# Grove_-_OLED_Display_0_96_SSD1315__v1_0.net
KiCad netlist of a schematic drawn in EAGLE
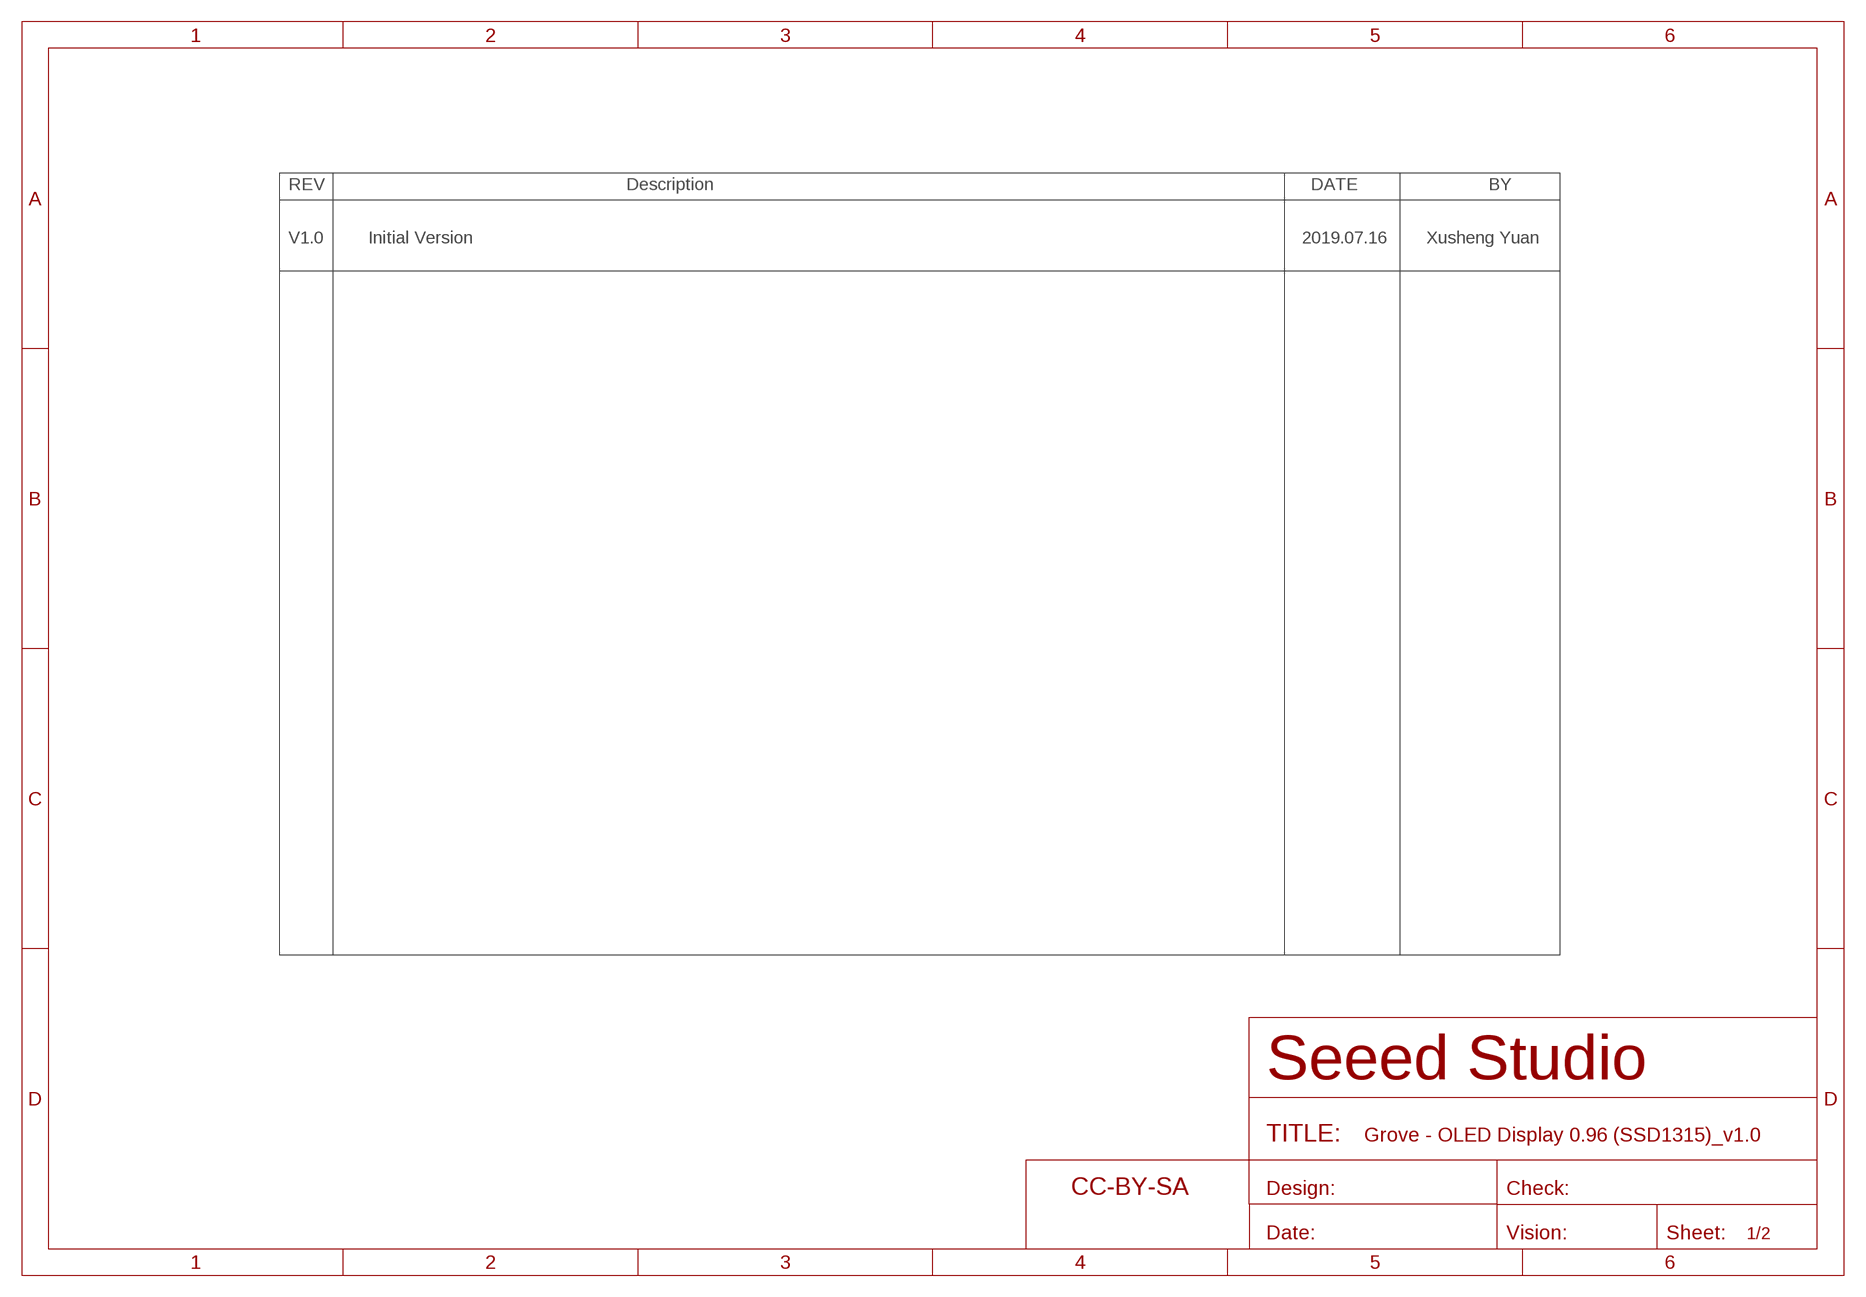
[diagram p0: schematic, sheet 1, part 1 of 2]
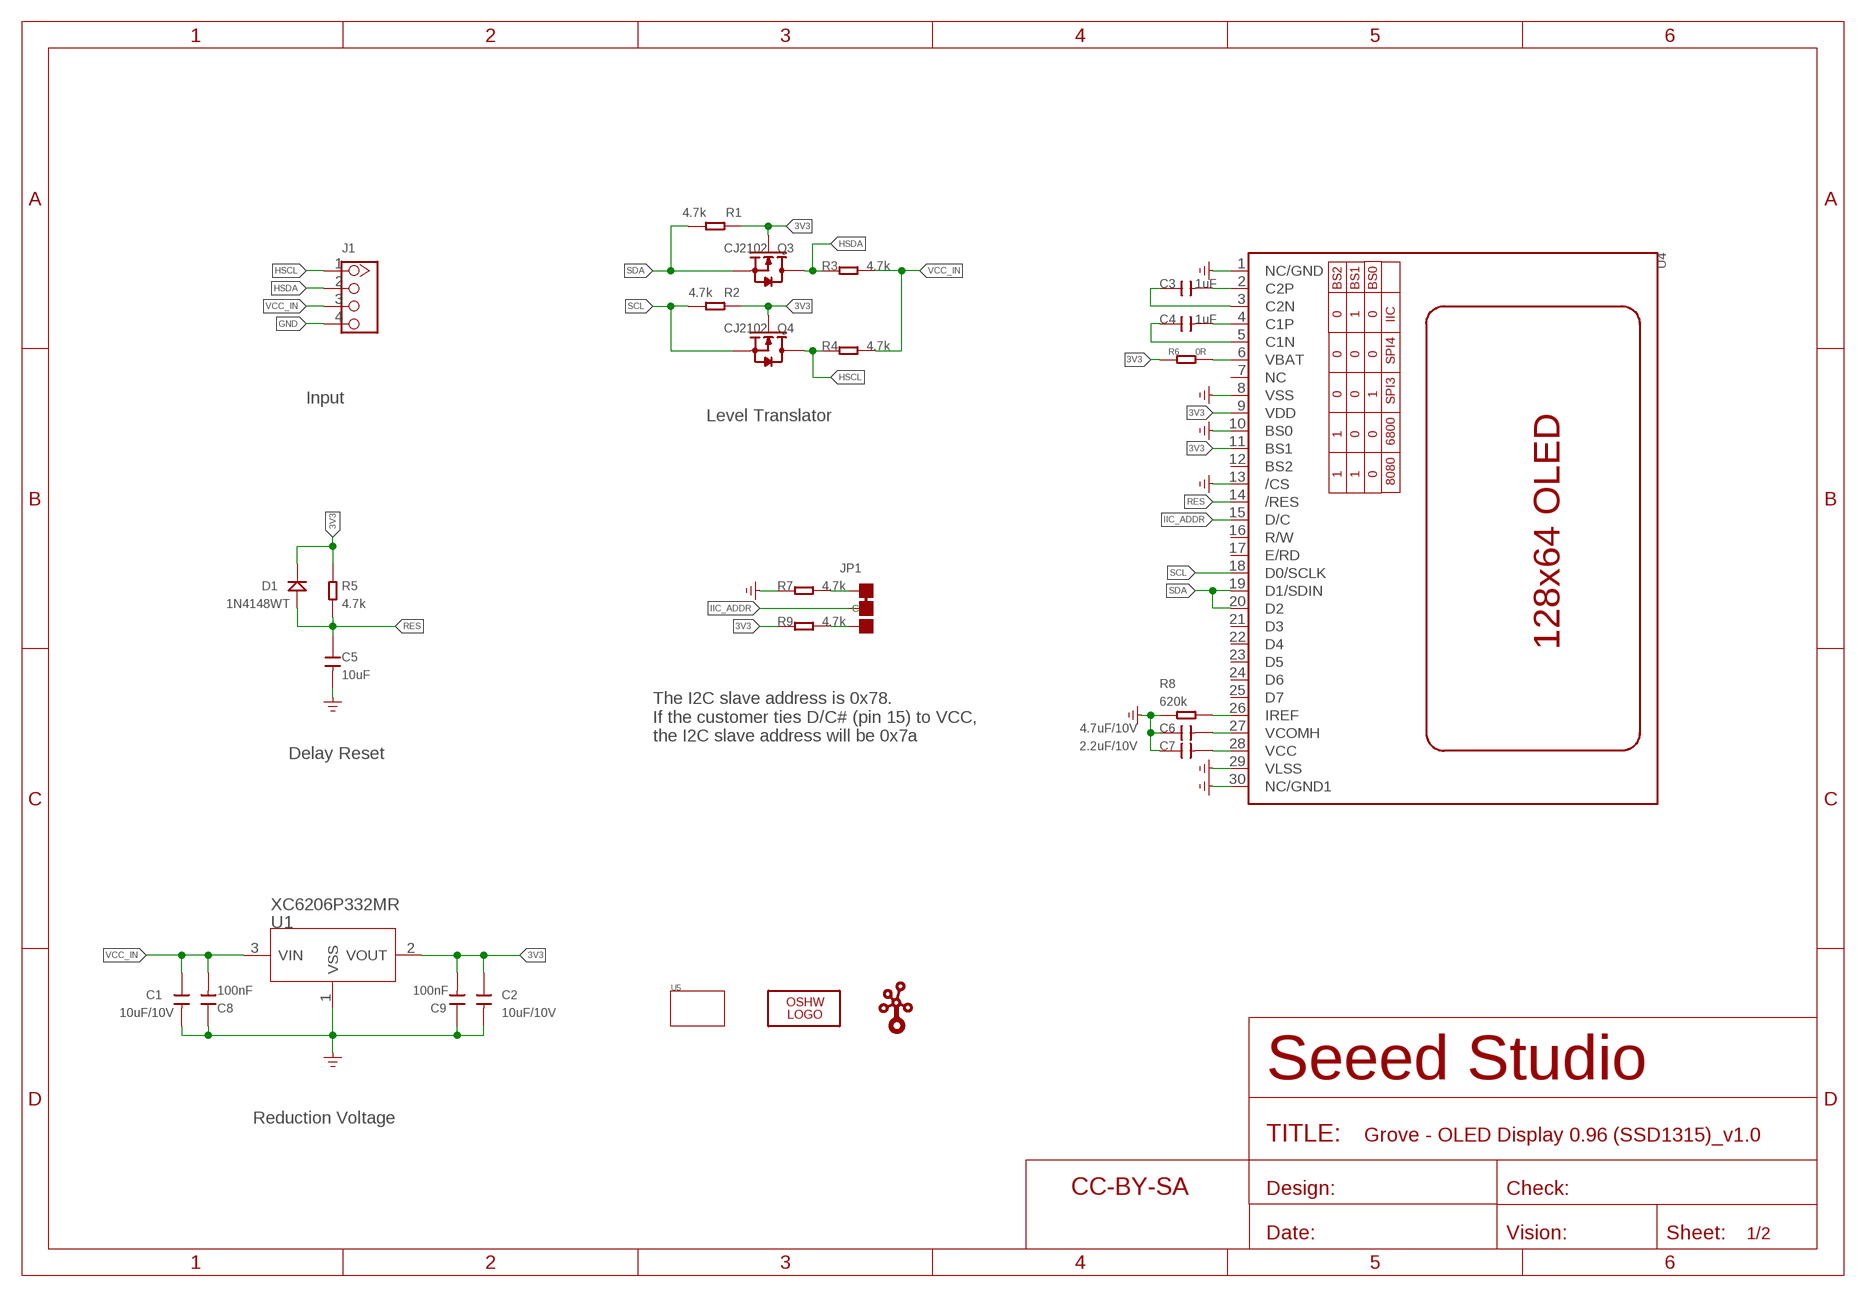
[diagram p1: schematic, sheet 1, part 2 of 2]

(export (version "E")
  (design (tool "Eeschema 10.0.6"))
  (components
    (comp (ref "C1")
      (value "10uF/10V")
      (footprint "eagle-import:C0603")
      (libsource (lib "eagle-import") (part "C-0603"))
    )
    (comp (ref "C2")
      (value "10uF/10V")
      (footprint "eagle-import:C0603")
      (libsource (lib "eagle-import") (part "C-0603"))
    )
    (comp (ref "C3")
      (value "1uF")
      (footprint "eagle-import:C0402")
      (libsource (lib "eagle-import") (part "C-0402"))
    )
    (comp (ref "C4")
      (value "1uF")
      (footprint "eagle-import:C0402")
      (libsource (lib "eagle-import") (part "C-0402"))
    )
    (comp (ref "C5")
      (value "10uF")
      (footprint "eagle-import:C0603")
      (libsource (lib "eagle-import") (part "C-0603"))
    )
    (comp (ref "C6")
      (value "4.7uF/10V")
      (footprint "eagle-import:C0603")
      (libsource (lib "eagle-import") (part "C-0603"))
    )
    (comp (ref "C7")
      (value "2.2uF/10V")
      (footprint "eagle-import:C0603")
      (libsource (lib "eagle-import") (part "C-0603"))
    )
    (comp (ref "C8")
      (value "100nF")
      (footprint "eagle-import:C0402")
      (libsource (lib "eagle-import") (part "C-0402"))
    )
    (comp (ref "C9")
      (value "100nF")
      (footprint "eagle-import:C0402")
      (libsource (lib "eagle-import") (part "C-0402"))
    )
    (comp (ref "D1")
      (value "1N4148WT")
      (footprint "eagle-import:SOD-523")
      (libsource (lib "eagle-import") (part "DIODE'0603'"))
    )
    (comp (ref "FR1")
      (value "SEEEDSTUDIO-OPEN-SCH-FRAME")
      (footprint "eagle-import:SEEEDSTUDIO-PCB-FRAME")
      (libsource (lib "eagle-import") (part "SEEEDSTUDIO-OPEN-SCH-FRAME"))
    )
    (comp (ref "FR2")
      (value "SEEEDSTUDIO-OPEN-SCH-FRAME")
      (footprint "eagle-import:SEEEDSTUDIO-PCB-FRAME")
      (libsource (lib "eagle-import") (part "SEEEDSTUDIO-OPEN-SCH-FRAME"))
    )
    (comp (ref "J1")
      (value "GROVE-CONNECTOR-DIP-320110033")
      (footprint "eagle-import:HW4-2.0")
      (libsource (lib "eagle-import") (part "GROVE-CONNECTOR-DIP-320110033"))
    )
    (comp (ref "JP1")
      (value "JP-3P-SHORT")
      (footprint "eagle-import:3P-SMD-SHORT")
      (libsource (lib "eagle-import") (part "JP-3P-SHORT"))
    )
    (comp (ref "LOGO1")
      (value "LOGO-OSHW-FILLX0150-NT")
      (footprint "eagle-import:OSHW_FILLX150_NOTEXT")
      (fields (field (name "PARTNO") "DNP"))
      (libsource (lib "eagle-import") (part "LOGO-OSHW-FILLX0150-NT"))
    )
    (comp (ref "Q3")
      (value "CJ2102")
      (footprint "eagle-import:SOT-323")
      (libsource (lib "eagle-import") (part "MOSFET-N'SI1304BDL'"))
    )
    (comp (ref "Q4")
      (value "CJ2102")
      (footprint "eagle-import:SOT-323")
      (libsource (lib "eagle-import") (part "MOSFET-N'SI1304BDL'"))
    )
    (comp (ref "R1")
      (value "4.7k")
      (footprint "eagle-import:R0402")
      (libsource (lib "eagle-import") (part "R-0402"))
    )
    (comp (ref "R2")
      (value "4.7k")
      (footprint "eagle-import:R0402")
      (libsource (lib "eagle-import") (part "R-0402"))
    )
    (comp (ref "R3")
      (value "4.7k")
      (footprint "eagle-import:R0402")
      (libsource (lib "eagle-import") (part "R-0402"))
    )
    (comp (ref "R4")
      (value "4.7k")
      (footprint "eagle-import:R0402")
      (libsource (lib "eagle-import") (part "R-0402"))
    )
    (comp (ref "R5")
      (value "4.7k")
      (footprint "eagle-import:R0402")
      (libsource (lib "eagle-import") (part "R-0402"))
    )
    (comp (ref "R6")
      (value "0R")
      (footprint "eagle-import:R0402")
      (libsource (lib "eagle-import") (part "R-0402"))
    )
    (comp (ref "R7")
      (value "4.7k")
      (footprint "eagle-import:R0402")
      (libsource (lib "eagle-import") (part "R-0402"))
    )
    (comp (ref "R8")
      (value "620k")
      (footprint "eagle-import:R0402")
      (libsource (lib "eagle-import") (part "R-0402"))
    )
    (comp (ref "R9")
      (value "4.7k")
      (footprint "eagle-import:R0402")
      (libsource (lib "eagle-import") (part "R-0402"))
    )
    (comp (ref "U$1")
      (value "LOGO-GROVETWIGLOGO_SMALL")
      (footprint "eagle-import:GROVE-SILK-SMALL")
      (fields (field (name "PARTNO") "DNP"))
      (libsource (lib "eagle-import") (part "LOGO-GROVETWIGLOGO_SMALL"))
    )
    (comp (ref "U1")
      (value "XC6206P332MR")
      (footprint "eagle-import:SOT-23")
      (libsource (lib "eagle-import") (part "PMIC-XC6206PMR"))
    )
    (comp (ref "U4")
      (value "OLED-12864-30P")
      (footprint "eagle-import:OLED30P-0.7-24.74X16.9MM")
      (libsource (lib "eagle-import") (part "OLED-12864-30P"))
    )
    (comp (ref "U5")
      (value "TWIG'2U'")
      (footprint "eagle-import:2U-DIM-W_DRILL")
      (libsource (lib "eagle-import") (part "TWIG'2U'"))
    )
  )
  (nets
    (net (code "1") (name "3V3") (class "Default")
      (node (ref "C2") (pin "1") (pinfunction "1_1") (pintype "passive"))
      (node (ref "C9") (pin "2") (pinfunction "2_2") (pintype "passive"))
      (node (ref "D1") (pin "-") (pinfunction "-_-") (pintype "passive"))
      (node (ref "Q3") (pin "1") (pinfunction "G_1") (pintype "passive"))
      (node (ref "Q4") (pin "1") (pinfunction "G_1") (pintype "passive"))
      (node (ref "R1") (pin "1") (pinfunction "1_1") (pintype "passive"))
      (node (ref "R2") (pin "2") (pinfunction "2_2") (pintype "passive"))
      (node (ref "R5") (pin "2") (pinfunction "2_2") (pintype "passive"))
      (node (ref "R6") (pin "1") (pinfunction "1_1") (pintype "passive"))
      (node (ref "R9") (pin "1") (pinfunction "1_1") (pintype "passive"))
      (node (ref "U1") (pin "2") (pinfunction "VOUT_2") (pintype "bidirectional"))
      (node (ref "U4") (pin "11") (pinfunction "BS1_11") (pintype "input"))
      (node (ref "U4") (pin "9") (pinfunction "VDD_9") (pintype "power_in"))
    )
    (net (code "2") (name "GND") (class "Default")
      (node (ref "C1") (pin "2") (pinfunction "2_2") (pintype "passive"))
      (node (ref "C2") (pin "2") (pinfunction "2_2") (pintype "passive"))
      (node (ref "C5") (pin "2") (pinfunction "2_2") (pintype "passive"))
      (node (ref "C6") (pin "1") (pinfunction "1_1") (pintype "passive"))
      (node (ref "C7") (pin "1") (pinfunction "1_1") (pintype "passive"))
      (node (ref "C8") (pin "1") (pinfunction "1_1") (pintype "passive"))
      (node (ref "C9") (pin "1") (pinfunction "1_1") (pintype "passive"))
      (node (ref "J1") (pin "4") (pinfunction "4_4") (pintype "bidirectional"))
      (node (ref "R7") (pin "1") (pinfunction "1_1") (pintype "passive"))
      (node (ref "R8") (pin "2") (pinfunction "2_2") (pintype "passive"))
      (node (ref "U1") (pin "1") (pinfunction "VSS_1") (pintype "bidirectional"))
      (node (ref "U4") (pin "1") (pinfunction "NC/GND_1") (pintype "input"))
      (node (ref "U4") (pin "10") (pinfunction "BS0_10") (pintype "input"))
      (node (ref "U4") (pin "13") (pinfunction "/CS_13") (pintype "input"))
      (node (ref "U4") (pin "29") (pinfunction "VLSS_29") (pintype "power_in"))
      (node (ref "U4") (pin "30") (pinfunction "NC/GND1_30") (pintype "input"))
      (node (ref "U4") (pin "8") (pinfunction "VSS_8") (pintype "power_in"))
    )
    (net (code "3") (name "HSCL") (class "Default")
      (node (ref "J1") (pin "1") (pinfunction "1_1") (pintype "bidirectional"))
      (node (ref "Q4") (pin "3") (pinfunction "D_3") (pintype "passive"))
      (node (ref "R4") (pin "1") (pinfunction "1_1") (pintype "passive"))
    )
    (net (code "4") (name "HSDA") (class "Default")
      (node (ref "J1") (pin "2") (pinfunction "2_2") (pintype "bidirectional"))
      (node (ref "Q3") (pin "3") (pinfunction "D_3") (pintype "passive"))
      (node (ref "R3") (pin "1") (pinfunction "1_1") (pintype "passive"))
    )
    (net (code "5") (name "IIC_ADDR") (class "Default")
      (node (ref "JP1") (pin "MM") (pinfunction "C_MM") (pintype "bidirectional"))
      (node (ref "U4") (pin "15") (pinfunction "D/C_15") (pintype "input"))
    )
    (net (code "6") (name "Net-(JP1-L)") (class "Default")
      (node (ref "JP1") (pin "11") (pinfunction "L_11") (pintype "bidirectional"))
      (node (ref "R7") (pin "2") (pinfunction "2_2") (pintype "passive"))
    )
    (net (code "7") (name "Net-(JP1-R)") (class "Default")
      (node (ref "JP1") (pin "00") (pinfunction "R_00") (pintype "bidirectional"))
      (node (ref "R9") (pin "2") (pinfunction "2_2") (pintype "passive"))
    )
    (net (code "8") (name "Net-(U4-C1N)") (class "Default")
      (node (ref "C4") (pin "1") (pinfunction "1_1") (pintype "passive"))
      (node (ref "U4") (pin "5") (pinfunction "C1N_5") (pintype "input"))
    )
    (net (code "9") (name "Net-(U4-C1P)") (class "Default")
      (node (ref "C4") (pin "2") (pinfunction "2_2") (pintype "passive"))
      (node (ref "U4") (pin "4") (pinfunction "C1P_4") (pintype "input"))
    )
    (net (code "10") (name "Net-(U4-C2N)") (class "Default")
      (node (ref "C3") (pin "1") (pinfunction "1_1") (pintype "passive"))
      (node (ref "U4") (pin "3") (pinfunction "C2N_3") (pintype "input"))
    )
    (net (code "11") (name "Net-(U4-C2P)") (class "Default")
      (node (ref "C3") (pin "2") (pinfunction "2_2") (pintype "passive"))
      (node (ref "U4") (pin "2") (pinfunction "C2P_2") (pintype "input"))
    )
    (net (code "12") (name "Net-(U4-IREF)") (class "Default")
      (node (ref "R8") (pin "1") (pinfunction "1_1") (pintype "passive"))
      (node (ref "U4") (pin "26") (pinfunction "IREF_26") (pintype "input"))
    )
    (net (code "13") (name "Net-(U4-VBAT)") (class "Default")
      (node (ref "R6") (pin "2") (pinfunction "2_2") (pintype "passive"))
      (node (ref "U4") (pin "6") (pinfunction "VBAT_6") (pintype "input"))
    )
    (net (code "14") (name "Net-(U4-VCC)") (class "Default")
      (node (ref "C7") (pin "2") (pinfunction "2_2") (pintype "passive"))
      (node (ref "U4") (pin "28") (pinfunction "VCC_28") (pintype "power_in"))
    )
    (net (code "15") (name "Net-(U4-VCOMH)") (class "Default")
      (node (ref "C6") (pin "2") (pinfunction "2_2") (pintype "passive"))
      (node (ref "U4") (pin "27") (pinfunction "VCOMH_27") (pintype "output"))
    )
    (net (code "16") (name "RES") (class "Default")
      (node (ref "C5") (pin "1") (pinfunction "1_1") (pintype "passive"))
      (node (ref "D1") (pin "+") (pinfunction "+_+") (pintype "passive"))
      (node (ref "R5") (pin "1") (pinfunction "1_1") (pintype "passive"))
      (node (ref "U4") (pin "14") (pinfunction "/RES_14") (pintype "input"))
    )
    (net (code "17") (name "SCL") (class "Default")
      (node (ref "Q4") (pin "2") (pinfunction "S_2") (pintype "passive"))
      (node (ref "R2") (pin "1") (pinfunction "1_1") (pintype "passive"))
      (node (ref "U4") (pin "18") (pinfunction "D0/SCLK_18") (pintype "bidirectional"))
    )
    (net (code "18") (name "SDA") (class "Default")
      (node (ref "Q3") (pin "2") (pinfunction "S_2") (pintype "passive"))
      (node (ref "R1") (pin "2") (pinfunction "2_2") (pintype "passive"))
      (node (ref "U4") (pin "19") (pinfunction "D1/SDIN_19") (pintype "bidirectional"))
      (node (ref "U4") (pin "20") (pinfunction "D2_20") (pintype "input"))
    )
    (net (code "19") (name "VCC_IN") (class "Default")
      (node (ref "C1") (pin "1") (pinfunction "1_1") (pintype "passive"))
      (node (ref "C8") (pin "2") (pinfunction "2_2") (pintype "passive"))
      (node (ref "J1") (pin "3") (pinfunction "3_3") (pintype "bidirectional"))
      (node (ref "R3") (pin "2") (pinfunction "2_2") (pintype "passive"))
      (node (ref "R4") (pin "2") (pinfunction "2_2") (pintype "passive"))
      (node (ref "U1") (pin "3") (pinfunction "VIN_3") (pintype "bidirectional"))
    )
    (net (code "20") (name "unconnected-(U4-BS2-Pad12)") (class "Default")
      (node (ref "U4") (pin "12") (pinfunction "BS2_12") (pintype "input"))
    )
    (net (code "21") (name "unconnected-(U4-D3-Pad21)") (class "Default")
      (node (ref "U4") (pin "21") (pinfunction "D3_21") (pintype "input"))
    )
    (net (code "22") (name "unconnected-(U4-D4-Pad22)") (class "Default")
      (node (ref "U4") (pin "22") (pinfunction "D4_22") (pintype "input"))
    )
    (net (code "23") (name "unconnected-(U4-D5-Pad23)") (class "Default")
      (node (ref "U4") (pin "23") (pinfunction "D5_23") (pintype "input"))
    )
    (net (code "24") (name "unconnected-(U4-D6-Pad24)") (class "Default")
      (node (ref "U4") (pin "24") (pinfunction "D6_24") (pintype "input"))
    )
    (net (code "25") (name "unconnected-(U4-D7-Pad25)") (class "Default")
      (node (ref "U4") (pin "25") (pinfunction "D7_25") (pintype "input"))
    )
    (net (code "26") (name "unconnected-(U4-E{slash}RD-Pad17)") (class "Default")
      (node (ref "U4") (pin "17") (pinfunction "E/RD_17") (pintype "input"))
    )
    (net (code "27") (name "unconnected-(U4-NC-Pad7)") (class "Default")
      (node (ref "U4") (pin "7") (pinfunction "NC_7") (pintype "no_connect"))
    )
    (net (code "28") (name "unconnected-(U4-R{slash}W-Pad16)") (class "Default")
      (node (ref "U4") (pin "16") (pinfunction "R/W_16") (pintype "input"))
    )
  )
)
